# 1_ADST32-Power.net
KiCad netlist of a schematic drawn in Altium Designer
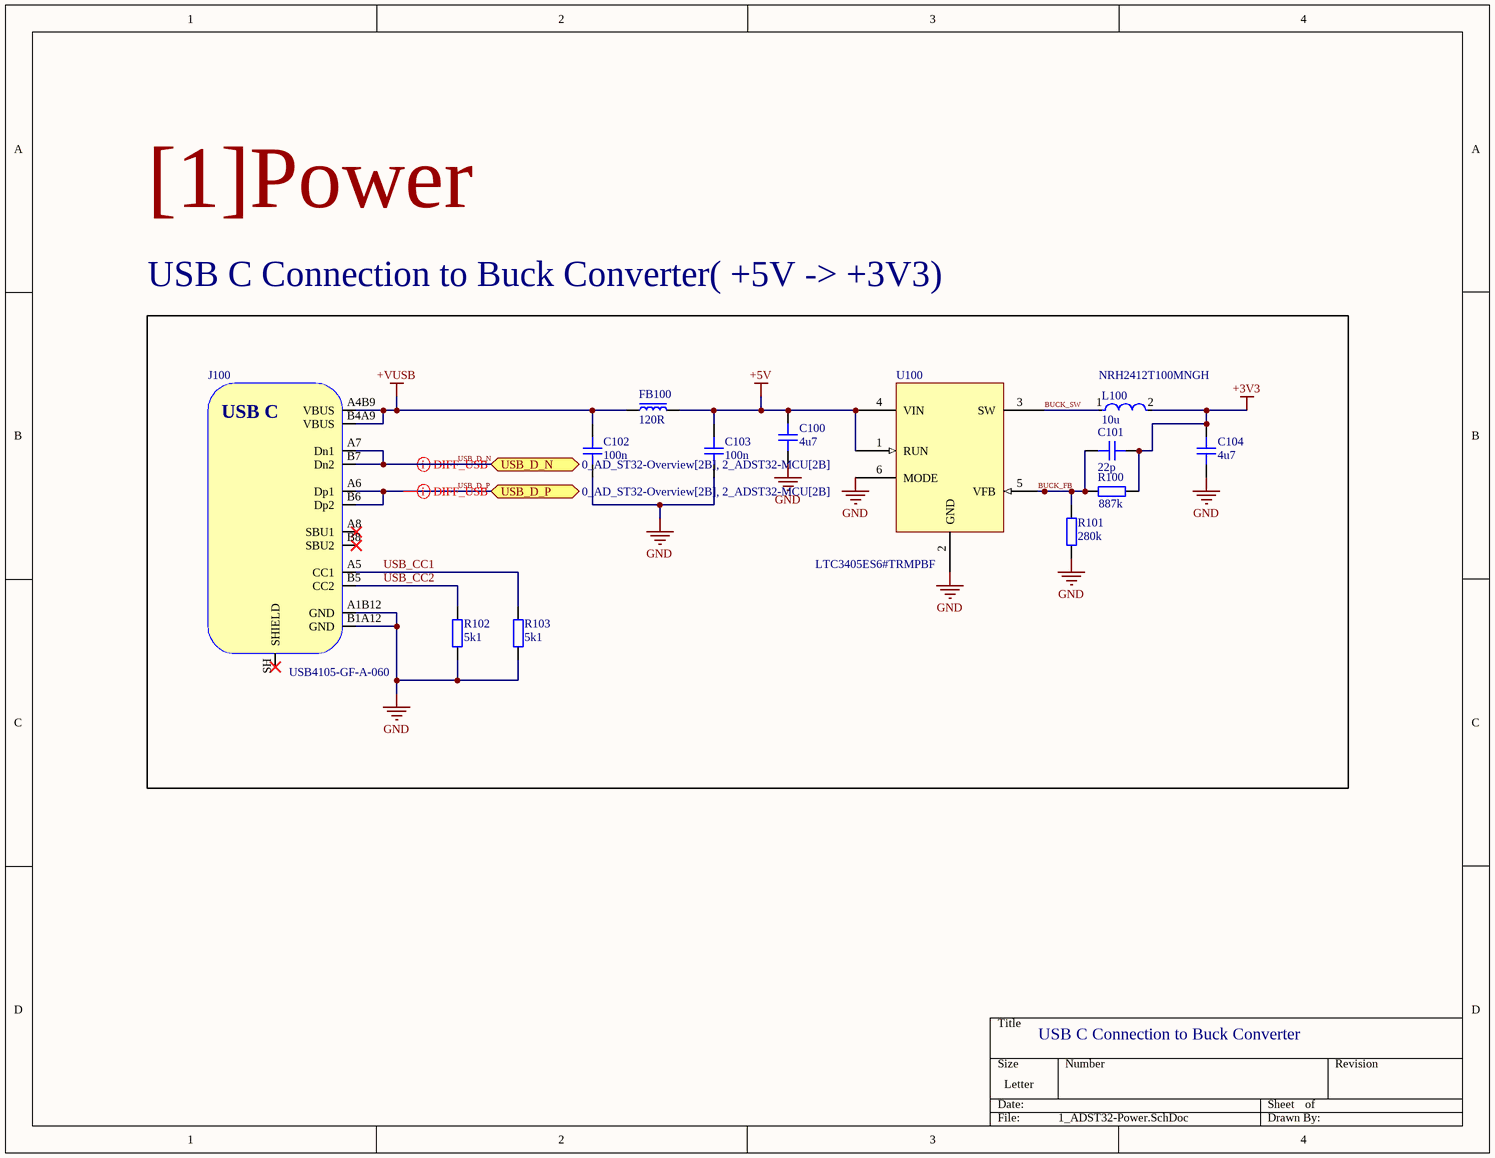
[diagram p0: 1_ADST32-Power.SchDoc]

(export (version "E")
  (design (tool "Eeschema 10.0.6"))
  (components
    (comp (ref "C100")
      (value "4u7")
      (footprint "CAP_0805")
      (description "Capacitor SMD 0805")
      (libsource (lib "Schematic-Lib-PhilsLab") (part "CAP_0805"))
    )
    (comp (ref "C101")
      (value "22p")
      (footprint "CAP_0603")
      (description "Capacitor SMD 0603")
      (libsource (lib "Schematic-Lib-PhilsLab") (part "CAP_0603"))
    )
    (comp (ref "C102")
      (value "100n")
      (footprint "CAP_0603")
      (description "Capacitor SMD 0603")
      (libsource (lib "Schematic-Lib-PhilsLab") (part "CAP_0603"))
    )
    (comp (ref "C103")
      (value "100n")
      (footprint "CAP_0603")
      (description "Capacitor SMD 0603")
      (libsource (lib "Schematic-Lib-PhilsLab") (part "CAP_0603"))
    )
    (comp (ref "C104")
      (value "4u7")
      (footprint "CAP_0805")
      (description "Capacitor SMD 0805")
      (libsource (lib "Schematic-Lib-PhilsLab") (part "CAP_0805"))
    )
    (comp (ref "FB100")
      (value "120R")
      (footprint "FB_0603")
      (description "Ferrite Bead SMD 0603")
      (libsource (lib "Schematic-Lib-PhilsLab") (part "FB_0603"))
    )
    (comp (ref "J100")
      (value "USB4105-GF-A-060")
      (footprint "USB4105-GF-A-060")
      (description "USB Connector Type C SMT 12 Pin")
      (fields (field (name "MANUFACTURER") "GCT"))
      (libsource (lib "Schematic-Lib-PhilsLab") (part "USB4105-GF-A-060"))
    )
    (comp (ref "L100")
      (value "10u")
      (footprint "FP-NRH2412-MFG")
      (description "Shielded Wirewound Inductor 10uH 20% 0.51A 0.72Ω SMD")
      (fields (field (name "TOLERANCE") "20%"))
      (libsource (lib "Altium Content Vault") (part "725321dda6339637d4d059423bc1c3c"))
    )
    (comp (ref "R100")
      (value "887k")
      (footprint "RES_0603")
      (description "Resistor SMD 0603")
      (libsource (lib "Schematic-Lib-PhilsLab") (part "RES_0603"))
    )
    (comp (ref "R101")
      (value "280k")
      (footprint "RES_0603")
      (description "Resistor SMD 0603")
      (libsource (lib "Schematic-Lib-PhilsLab") (part "RES_0603"))
    )
    (comp (ref "R102")
      (value "5k1")
      (footprint "RES_0603")
      (description "Resistor SMD 0603")
      (libsource (lib "Schematic-Lib-PhilsLab") (part "RES_0603"))
    )
    (comp (ref "R103")
      (value "5k1")
      (footprint "RES_0603")
      (description "Resistor SMD 0603")
      (libsource (lib "Schematic-Lib-PhilsLab") (part "RES_0603"))
    )
    (comp (ref "U100")
      (value "LTC3405ES6#TRMPBF")
      (footprint "SOT-23-6")
      (description "1.5MHz, 300mA\r\nSynchronous Step-Down\r\nRegulator in ThinSOT")
      (fields (field (name "MANUFACTURER") "Analog Devices"))
      (libsource (lib "Schematic-Lib-PhilsLab") (part "LTC3405ES6#TRMPBF"))
    )
  )
  (nets
    (net (code "1") (name "+3V3") (class "Default")
      (node (ref "C101") (pin "1") (pinfunction "1_1") (pintype "passive"))
      (node (ref "C104") (pin "2") (pinfunction "2_2") (pintype "passive"))
      (node (ref "L100") (pin "2") (pinfunction "2_2") (pintype "passive"))
      (node (ref "R100") (pin "1") (pinfunction "1_1") (pintype "passive"))
    )
    (net (code "2") (name "+5V") (class "Default")
      (node (ref "C100") (pin "2") (pinfunction "2_2") (pintype "passive"))
      (node (ref "C103") (pin "2") (pinfunction "2_2") (pintype "passive"))
      (node (ref "FB100") (pin "2") (pinfunction "2_2") (pintype "passive"))
      (node (ref "U100") (pin "1") (pinfunction "RUN_1") (pintype "input"))
      (node (ref "U100") (pin "4") (pinfunction "VIN_4") (pintype "power_in"))
    )
    (net (code "3") (name "+VUSB") (class "Default")
      (node (ref "C102") (pin "2") (pinfunction "2_2") (pintype "passive"))
      (node (ref "FB100") (pin "1") (pinfunction "1_1") (pintype "passive"))
      (node (ref "J100") (pin "A4B9") (pinfunction "VBUS_A4B9") (pintype "passive"))
      (node (ref "J100") (pin "B4A9") (pinfunction "VBUS_B4A9") (pintype "passive"))
    )
    (net (code "4") (name "/BUCK_FB") (class "Default")
      (node (ref "C101") (pin "2") (pinfunction "2_2") (pintype "passive"))
      (node (ref "R100") (pin "2") (pinfunction "2_2") (pintype "passive"))
      (node (ref "R101") (pin "2") (pinfunction "2_2") (pintype "passive"))
      (node (ref "U100") (pin "5") (pinfunction "VFB_5") (pintype "input"))
    )
    (net (code "5") (name "/BUCK_SW") (class "Default")
      (node (ref "L100") (pin "1") (pinfunction "1_1") (pintype "passive"))
      (node (ref "U100") (pin "3") (pinfunction "SW_3") (pintype "power_in"))
    )
    (net (code "6") (name "/USB_CC1") (class "Default")
      (node (ref "J100") (pin "A5") (pinfunction "CC1_A5") (pintype "passive"))
      (node (ref "R103") (pin "2") (pinfunction "2_2") (pintype "passive"))
    )
    (net (code "7") (name "/USB_CC2") (class "Default")
      (node (ref "J100") (pin "B5") (pinfunction "CC2_B5") (pintype "passive"))
      (node (ref "R102") (pin "2") (pinfunction "2_2") (pintype "passive"))
    )
    (net (code "8") (name "/USB_D_N") (class "Default")
      (node (ref "J100") (pin "A7") (pinfunction "Dn1_A7") (pintype "passive"))
      (node (ref "J100") (pin "B7") (pinfunction "Dn2_B7") (pintype "passive"))
    )
    (net (code "9") (name "/USB_D_P") (class "Default")
      (node (ref "J100") (pin "A6") (pinfunction "Dp1_A6") (pintype "passive"))
      (node (ref "J100") (pin "B6") (pinfunction "Dp2_B6") (pintype "passive"))
    )
    (net (code "10") (name "GND") (class "Default")
      (node (ref "C100") (pin "1") (pinfunction "1_1") (pintype "passive"))
      (node (ref "C102") (pin "1") (pinfunction "1_1") (pintype "passive"))
      (node (ref "C103") (pin "1") (pinfunction "1_1") (pintype "passive"))
      (node (ref "C104") (pin "1") (pinfunction "1_1") (pintype "passive"))
      (node (ref "J100") (pin "A1B12") (pinfunction "GND_A1B12") (pintype "passive"))
      (node (ref "J100") (pin "B1A12") (pinfunction "GND_B1A12") (pintype "passive"))
      (node (ref "R101") (pin "1") (pinfunction "1_1") (pintype "passive"))
      (node (ref "R102") (pin "1") (pinfunction "1_1") (pintype "passive"))
      (node (ref "R103") (pin "1") (pinfunction "1_1") (pintype "passive"))
      (node (ref "U100") (pin "2") (pinfunction "GND_2") (pintype "power_in"))
      (node (ref "U100") (pin "6") (pinfunction "MODE_6") (pintype "passive"))
    )
    (net (code "11") (name "unconnected-(J100-SBU1-PadA8)") (class "Default")
      (node (ref "J100") (pin "A8") (pinfunction "SBU1_A8") (pintype "passive+no_connect"))
    )
    (net (code "12") (name "unconnected-(J100-SBU2-PadB8)") (class "Default")
      (node (ref "J100") (pin "B8") (pinfunction "SBU2_B8") (pintype "passive+no_connect"))
    )
    (net (code "13") (name "unconnected-(J100-SHIELD-PadSH)") (class "Default")
      (node (ref "J100") (pin "SH") (pinfunction "SHIELD_SH") (pintype "passive+no_connect"))
    )
  )
)
